# untitled.net
KiCad netlist of a schematic drawn in EAGLE
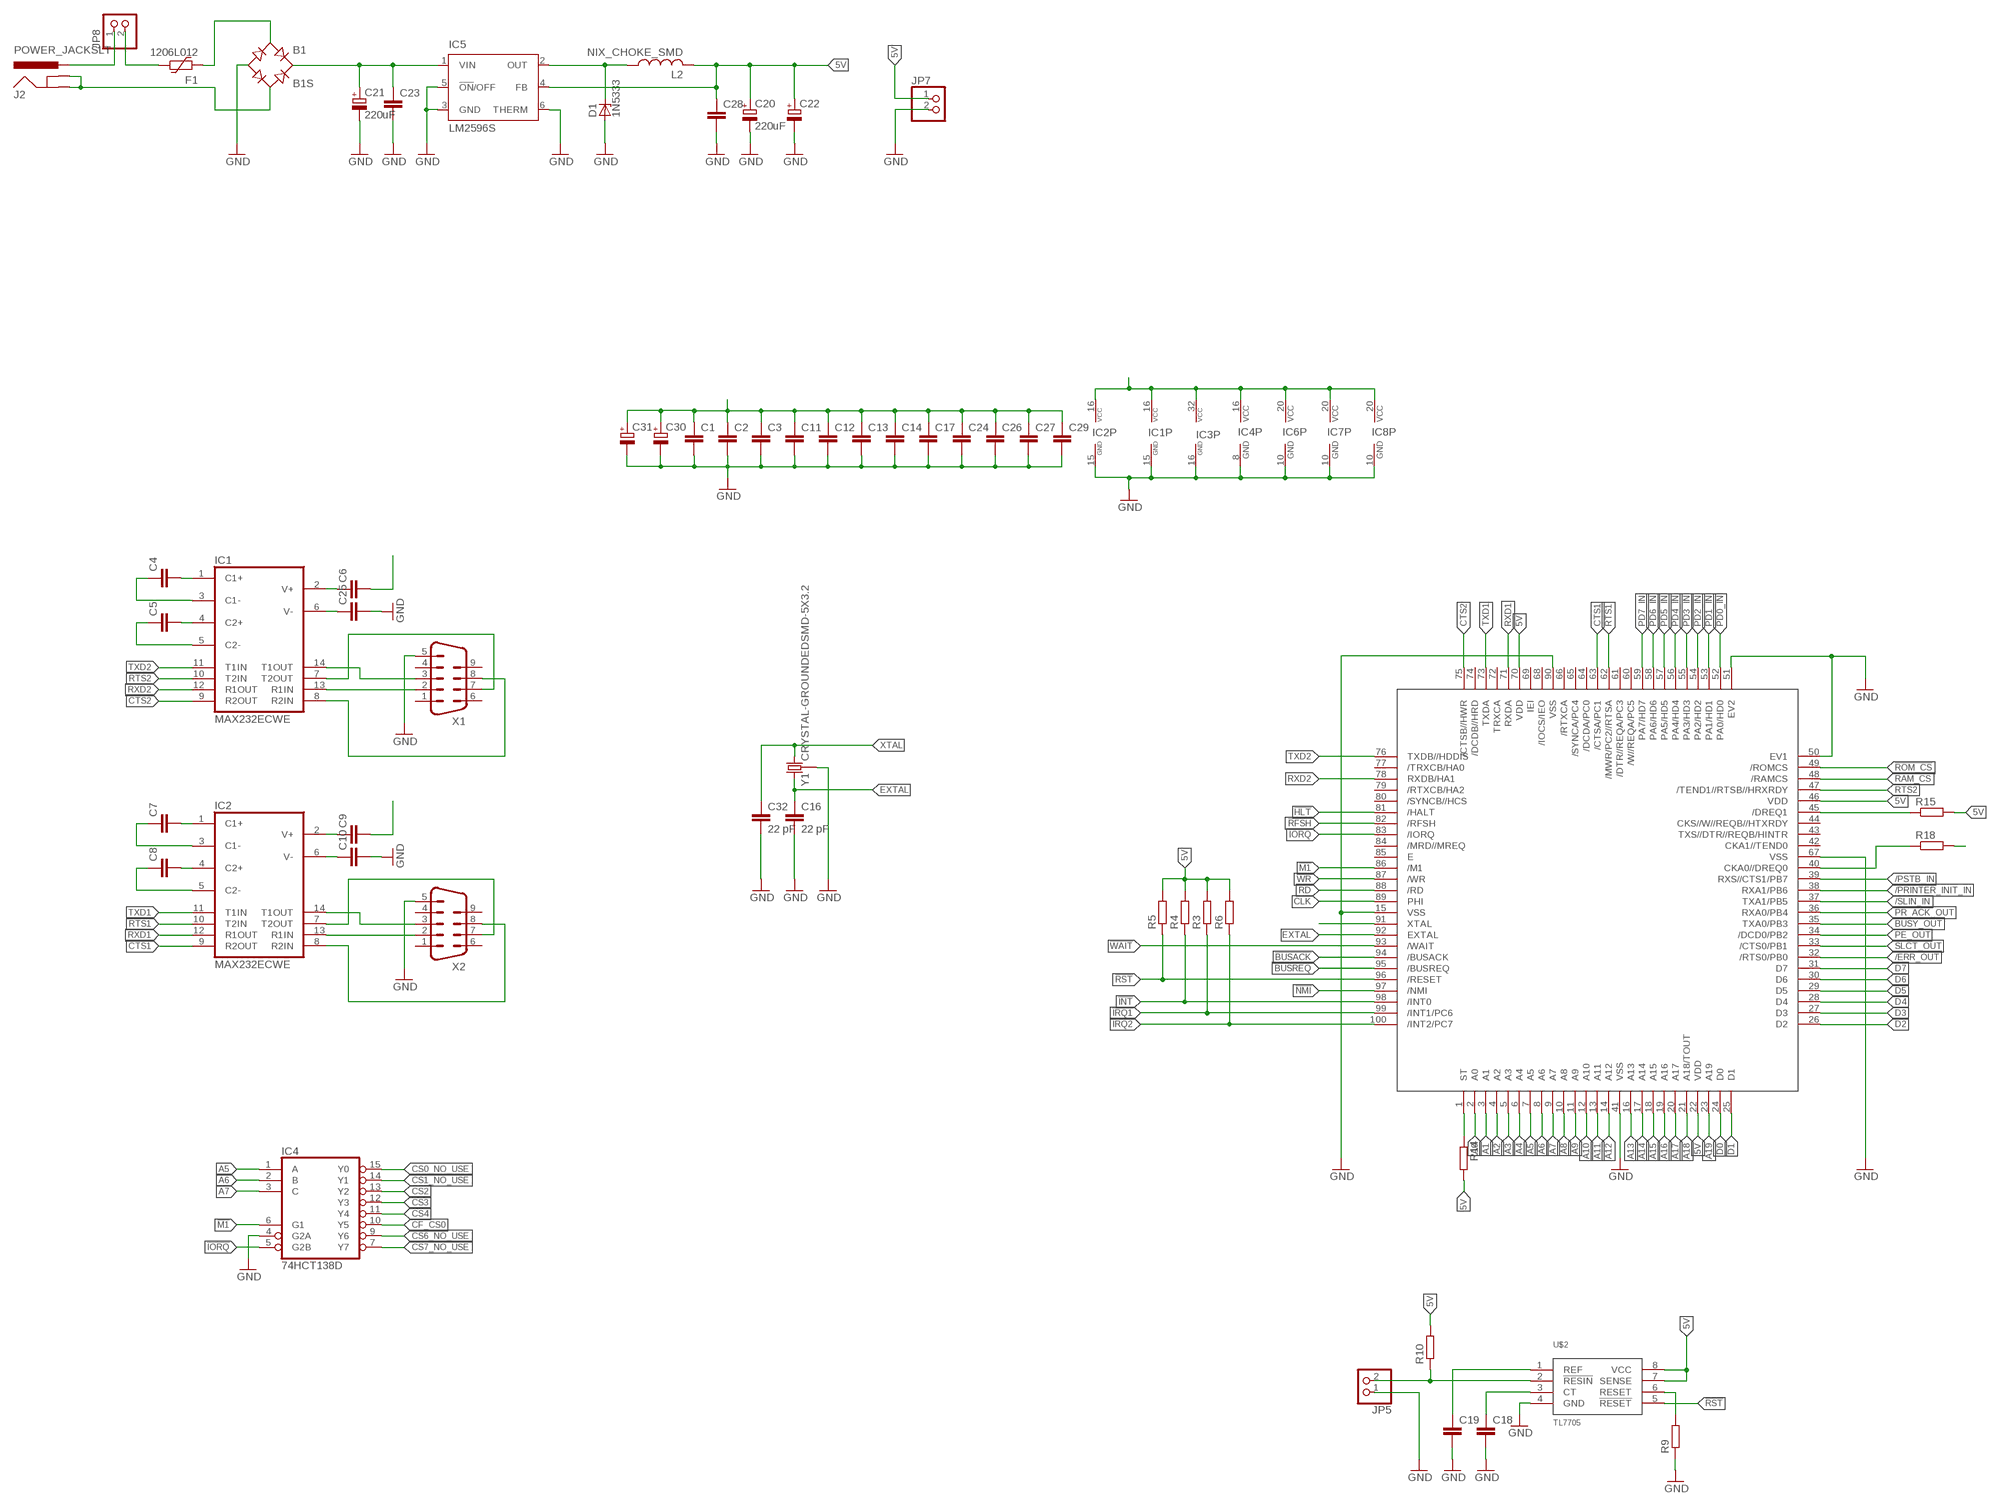
[diagram p0: schematic, sheet 1, part 1 of 2]
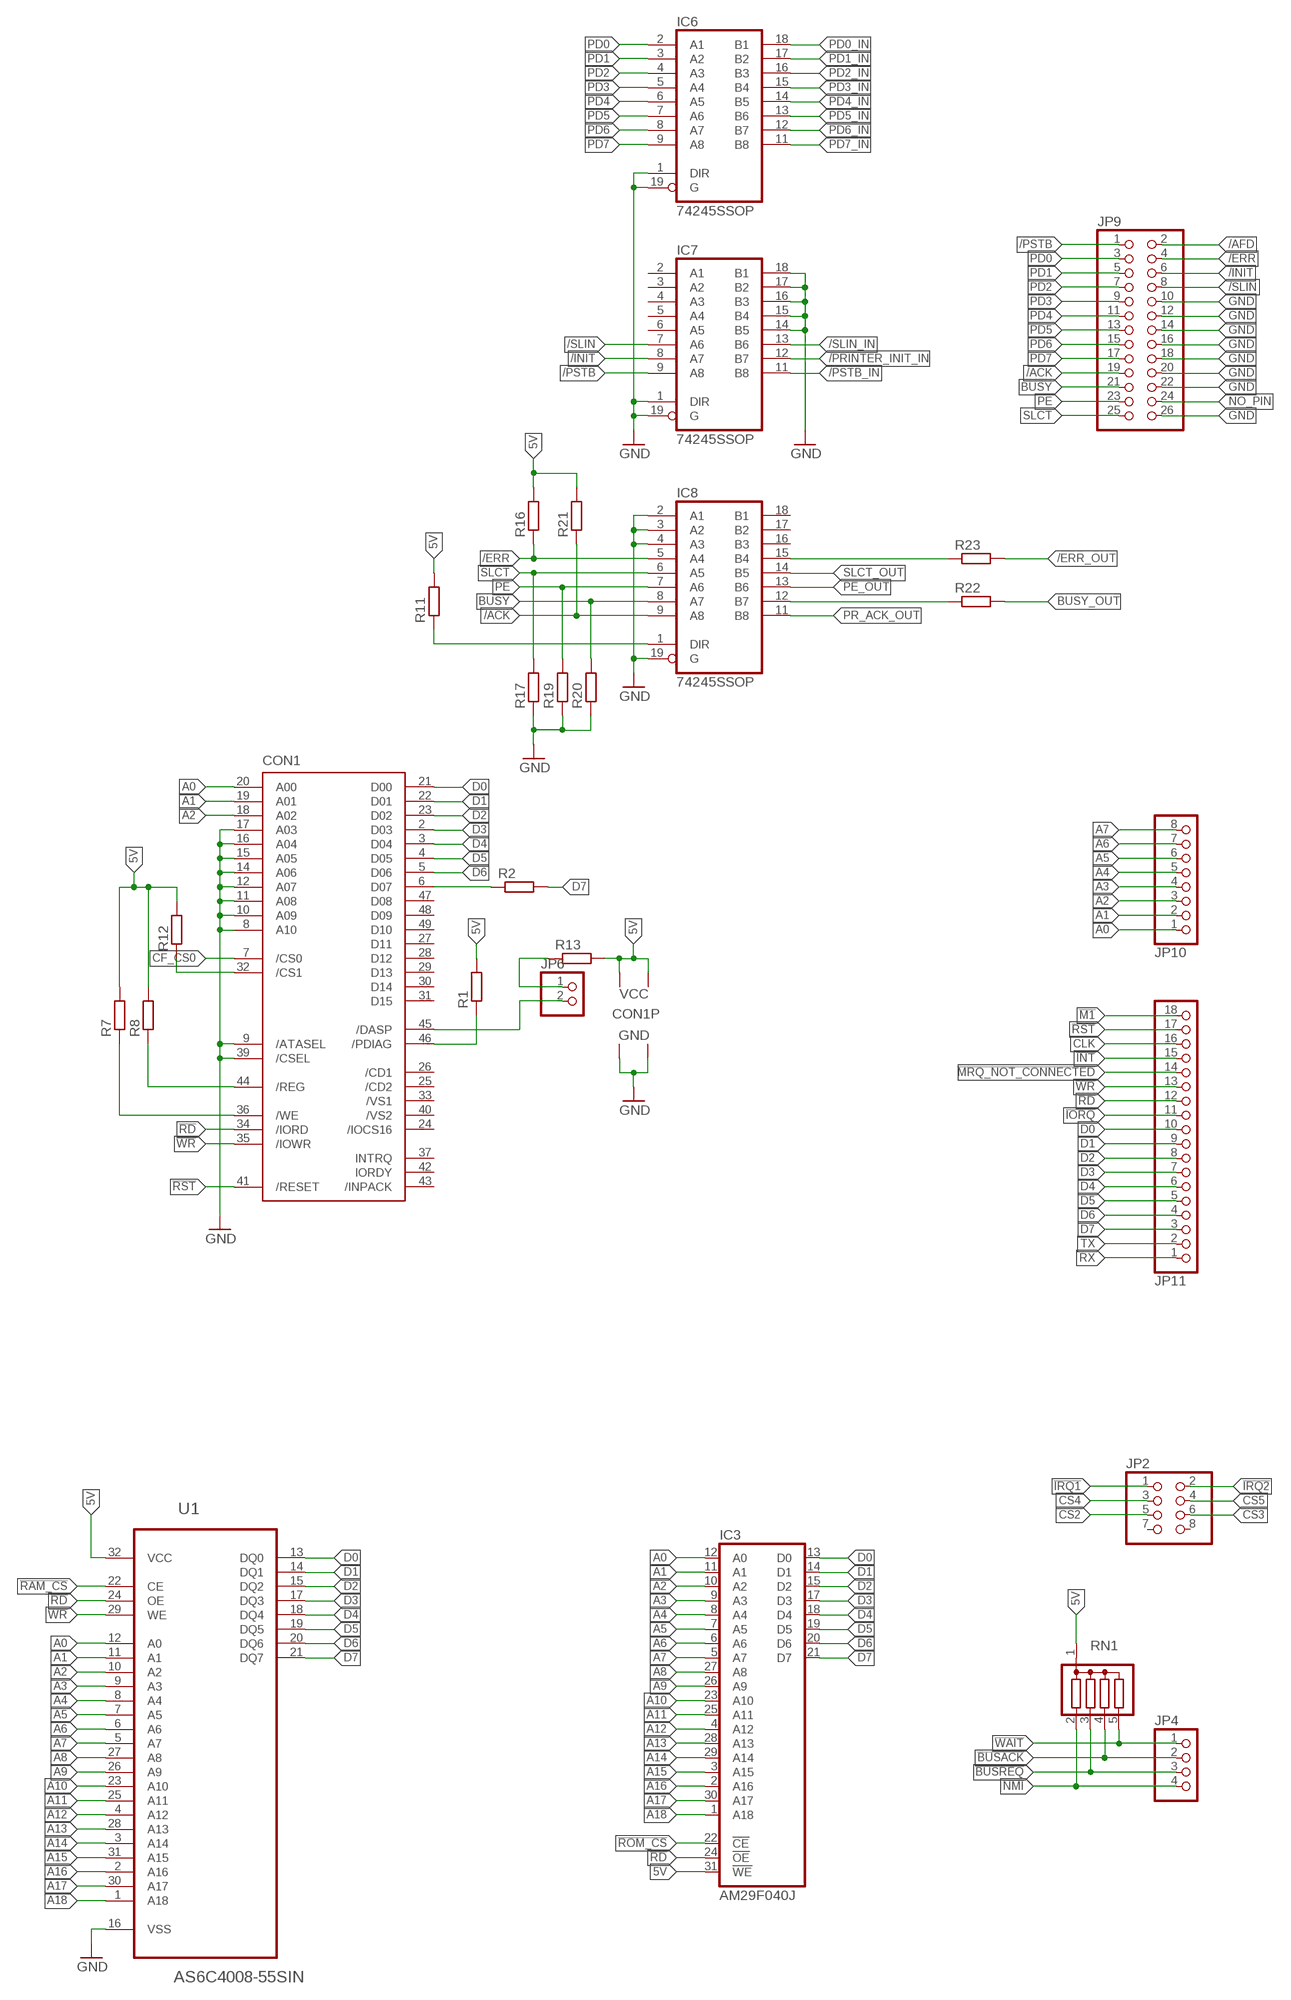
[diagram p1: schematic, sheet 1, part 2 of 2]

(export (version "E")
  (design (tool "Eeschema 10.0.6"))
  (components
    (comp (ref "B1")
      (value "B1S")
      (footprint "eagle-import:MBS")
      (libsource (lib "eagle-import") (part "BS1"))
    )
    (comp (ref "C1")
      (value "C-EUC0603")
      (footprint "eagle-import:C0603")
      (libsource (lib "eagle-import") (part "C-EUC0603"))
    )
    (comp (ref "C2")
      (value "C-EUC0603")
      (footprint "eagle-import:C0603")
      (libsource (lib "eagle-import") (part "C-EUC0603"))
    )
    (comp (ref "C3")
      (value "C-EUC0402")
      (footprint "eagle-import:C0402")
      (libsource (lib "eagle-import") (part "C-EUC0402"))
    )
    (comp (ref "C4")
      (value "C-EUC0603")
      (footprint "eagle-import:C0603")
      (libsource (lib "eagle-import") (part "C-EUC0603"))
    )
    (comp (ref "C5")
      (value "C-EUC0603")
      (footprint "eagle-import:C0603")
      (libsource (lib "eagle-import") (part "C-EUC0603"))
    )
    (comp (ref "C6")
      (value "C-EUC0603")
      (footprint "eagle-import:C0603")
      (libsource (lib "eagle-import") (part "C-EUC0603"))
    )
    (comp (ref "C7")
      (value "C-EUC0603")
      (footprint "eagle-import:C0603")
      (libsource (lib "eagle-import") (part "C-EUC0603"))
    )
    (comp (ref "C8")
      (value "C-EUC0603")
      (footprint "eagle-import:C0603")
      (libsource (lib "eagle-import") (part "C-EUC0603"))
    )
    (comp (ref "C9")
      (value "C-EUC0603")
      (footprint "eagle-import:C0603")
      (libsource (lib "eagle-import") (part "C-EUC0603"))
    )
    (comp (ref "C10")
      (value "C-EUC0603")
      (footprint "eagle-import:C0603")
      (libsource (lib "eagle-import") (part "C-EUC0603"))
    )
    (comp (ref "C11")
      (value "C-EUC0603")
      (footprint "eagle-import:C0603")
      (libsource (lib "eagle-import") (part "C-EUC0603"))
    )
    (comp (ref "C12")
      (value "C-EUC0603")
      (footprint "eagle-import:C0603")
      (libsource (lib "eagle-import") (part "C-EUC0603"))
    )
    (comp (ref "C13")
      (value "C-EUC0402")
      (footprint "eagle-import:C0402")
      (libsource (lib "eagle-import") (part "C-EUC0402"))
    )
    (comp (ref "C14")
      (value "C-EUC0603")
      (footprint "eagle-import:C0603")
      (libsource (lib "eagle-import") (part "C-EUC0603"))
    )
    (comp (ref "C16")
      (value "22 pF")
      (footprint "eagle-import:C0603")
      (libsource (lib "eagle-import") (part "C-EUC0603"))
    )
    (comp (ref "C17")
      (value "C-EUC0603")
      (footprint "eagle-import:C0603")
      (libsource (lib "eagle-import") (part "C-EUC0603"))
    )
    (comp (ref "C18")
      (value "C-EUC0603")
      (footprint "eagle-import:C0603")
      (libsource (lib "eagle-import") (part "C-EUC0603"))
    )
    (comp (ref "C19")
      (value "C-EUC0603")
      (footprint "eagle-import:C0603")
      (libsource (lib "eagle-import") (part "C-EUC0603"))
    )
    (comp (ref "C20")
      (value "220uF")
      (footprint "eagle-import:153CLV-0810")
      (libsource (lib "eagle-import") (part "CPOL-EU153CLV-0810"))
    )
    (comp (ref "C21")
      (value "220uF")
      (footprint "eagle-import:153CLV-0810")
      (libsource (lib "eagle-import") (part "CPOL-EU153CLV-0810"))
    )
    (comp (ref "C22")
      (value "CPOL-EUSMCC")
      (footprint "eagle-import:SMC_C")
      (libsource (lib "eagle-import") (part "CPOL-EUSMCC"))
    )
    (comp (ref "C23")
      (value "C-EUC0603")
      (footprint "eagle-import:C0603")
      (libsource (lib "eagle-import") (part "C-EUC0603"))
    )
    (comp (ref "C24")
      (value "C-EUC0603")
      (footprint "eagle-import:C0603")
      (libsource (lib "eagle-import") (part "C-EUC0603"))
    )
    (comp (ref "C25")
      (value "C-EUC0603")
      (footprint "eagle-import:C0603")
      (libsource (lib "eagle-import") (part "C-EUC0603"))
    )
    (comp (ref "C26")
      (value "C-EUC0402")
      (footprint "eagle-import:C0402")
      (libsource (lib "eagle-import") (part "C-EUC0402"))
    )
    (comp (ref "C27")
      (value "C-EUC0402")
      (footprint "eagle-import:C0402")
      (libsource (lib "eagle-import") (part "C-EUC0402"))
    )
    (comp (ref "C28")
      (value "C-EUC0603")
      (footprint "eagle-import:C0603")
      (libsource (lib "eagle-import") (part "C-EUC0603"))
    )
    (comp (ref "C29")
      (value "C-EUC0603")
      (footprint "eagle-import:C0603")
      (libsource (lib "eagle-import") (part "C-EUC0603"))
    )
    (comp (ref "C30")
      (value "CPOL-EUSMCB")
      (footprint "eagle-import:SMC_B")
      (libsource (lib "eagle-import") (part "CPOL-EUSMCB"))
    )
    (comp (ref "C31")
      (value "CPOL-EUSMCB")
      (footprint "eagle-import:SMC_B")
      (libsource (lib "eagle-import") (part "CPOL-EUSMCB"))
    )
    (comp (ref "C32")
      (value "22 pF")
      (footprint "eagle-import:C0603")
      (libsource (lib "eagle-import") (part "C-EUC0603"))
    )
    (comp (ref "CON1")
      (value "CF-CARD-IDE_MODE")
      (footprint "eagle-import:MI20-50PD-SF")
      (libsource (lib "eagle-import") (part "CF-CARD-IDE_MODE"))
    )
    (comp (ref "D1")
      (value "1N5333")
      (footprint "eagle-import:C1702-15")
      (libsource (lib "eagle-import") (part "1N5333"))
    )
    (comp (ref "F1")
      (value "1206L012")
      (footprint "eagle-import:1206L")
      (fields (field (name "MF") "Littelfuse"))
      (libsource (lib "eagle-import") (part "?1206L012"))
    )
    (comp (ref "IC1")
      (value "MAX232ECWE")
      (footprint "eagle-import:SO16L")
      (fields (field (name "MF") "MAXIM") (field (name "MPN") "MAX232ECWE+"))
      (libsource (lib "eagle-import") (part "MAX232ECWE"))
    )
    (comp (ref "IC2")
      (value "MAX232ECWE")
      (footprint "eagle-import:SO16L")
      (fields (field (name "MF") "MAXIM") (field (name "MPN") "MAX232ECWE+"))
      (libsource (lib "eagle-import") (part "MAX232ECWE"))
    )
    (comp (ref "IC3")
      (value "AM29F040J")
      (footprint "eagle-import:PLCC32R")
      (libsource (lib "eagle-import") (part "AM29F040J"))
    )
    (comp (ref "IC4")
      (value "74HCT138D")
      (footprint "eagle-import:SO16")
      (libsource (lib "eagle-import") (part "74138DHCT"))
    )
    (comp (ref "IC5")
      (value "LM2596S")
      (footprint "eagle-import:TO263-5")
      (fields (field (name "MF") "NATIONAL SEMICONDUCTOR") (field (name "MPN") "LM2596S-ADJ/NOPB"))
      (libsource (lib "eagle-import") (part "LM2596S"))
    )
    (comp (ref "IC6")
      (value "74245SSOP")
      (footprint "eagle-import:SSOP20")
      (libsource (lib "eagle-import") (part "74245SSOP"))
    )
    (comp (ref "IC7")
      (value "74245SSOP")
      (footprint "eagle-import:SSOP20")
      (libsource (lib "eagle-import") (part "74245SSOP"))
    )
    (comp (ref "IC8")
      (value "74245SSOP")
      (footprint "eagle-import:SSOP20")
      (libsource (lib "eagle-import") (part "74245SSOP"))
    )
    (comp (ref "J2")
      (value "POWER_JACKSLT")
      (footprint "eagle-import:POWER_JACK_SLOT")
      (libsource (lib "eagle-import") (part "POWER_JACKSLT"))
    )
    (comp (ref "JP2")
      (value "PINHD-2X4")
      (footprint "eagle-import:2X04")
      (libsource (lib "eagle-import") (part "PINHD-2X4"))
    )
    (comp (ref "JP4")
      (value "PINHD-1X4")
      (footprint "eagle-import:1X04")
      (libsource (lib "eagle-import") (part "PINHD-1X4"))
    )
    (comp (ref "JP5")
      (value "PINHD-1X2")
      (footprint "eagle-import:1X02")
      (libsource (lib "eagle-import") (part "PINHD-1X2"))
    )
    (comp (ref "JP6")
      (value "PINHD-1X2")
      (footprint "eagle-import:1X02")
      (libsource (lib "eagle-import") (part "PINHD-1X2"))
    )
    (comp (ref "JP7")
      (value "PINHD-1X2")
      (footprint "eagle-import:1X02")
      (libsource (lib "eagle-import") (part "PINHD-1X2"))
    )
    (comp (ref "JP8")
      (value "PINHD-1X2")
      (footprint "eagle-import:1X02")
      (libsource (lib "eagle-import") (part "PINHD-1X2"))
    )
    (comp (ref "JP9")
      (value "PINHD-2X13_2.54-SMD")
      (footprint "eagle-import:2X13SMD")
      (libsource (lib "eagle-import") (part "PINHD-2X13_2.54-SMD"))
    )
    (comp (ref "JP10")
      (value "PINHD-1X8")
      (footprint "eagle-import:1X08")
      (libsource (lib "eagle-import") (part "PINHD-1X8"))
    )
    (comp (ref "JP11")
      (value "PINHD-1X18")
      (footprint "eagle-import:1X18")
      (libsource (lib "eagle-import") (part "PINHD-1X18"))
    )
    (comp (ref "L2")
      (value "NIX_CHOKE_SMD")
      (footprint "eagle-import:NIX_CHOKE_SMD")
      (libsource (lib "eagle-import") (part "NIX_CHOKE_SMD"))
    )
    (comp (ref "R1")
      (value "R-EU_R0603")
      (footprint "eagle-import:R0603")
      (libsource (lib "eagle-import") (part "R-EU_R0603"))
    )
    (comp (ref "R2")
      (value "R-EU_R0603")
      (footprint "eagle-import:R0603")
      (libsource (lib "eagle-import") (part "R-EU_R0603"))
    )
    (comp (ref "R3")
      (value "R-EU_R0402")
      (footprint "eagle-import:R0402")
      (libsource (lib "eagle-import") (part "R-EU_R0402"))
    )
    (comp (ref "R4")
      (value "R-EU_R0603")
      (footprint "eagle-import:R0603")
      (libsource (lib "eagle-import") (part "R-EU_R0603"))
    )
    (comp (ref "R5")
      (value "R-EU_R1206")
      (footprint "eagle-import:R1206")
      (libsource (lib "eagle-import") (part "R-EU_R1206"))
    )
    (comp (ref "R6")
      (value "R-EU_R0603")
      (footprint "eagle-import:R0603")
      (libsource (lib "eagle-import") (part "R-EU_R0603"))
    )
    (comp (ref "R7")
      (value "R-EU_R0603")
      (footprint "eagle-import:R0603")
      (libsource (lib "eagle-import") (part "R-EU_R0603"))
    )
    (comp (ref "R8")
      (value "R-EU_R0603")
      (footprint "eagle-import:R0603")
      (libsource (lib "eagle-import") (part "R-EU_R0603"))
    )
    (comp (ref "R9")
      (value "R-EU_R0603")
      (footprint "eagle-import:R0603")
      (libsource (lib "eagle-import") (part "R-EU_R0603"))
    )
    (comp (ref "R10")
      (value "R-EU_M1206")
      (footprint "eagle-import:M1206")
      (libsource (lib "eagle-import") (part "R-EU_M1206"))
    )
    (comp (ref "R11")
      (value "R-EU_R0603")
      (footprint "eagle-import:R0603")
      (libsource (lib "eagle-import") (part "R-EU_R0603"))
    )
    (comp (ref "R12")
      (value "R-EU_R0603")
      (footprint "eagle-import:R0603")
      (libsource (lib "eagle-import") (part "R-EU_R0603"))
    )
    (comp (ref "R13")
      (value "R-EU_R0603")
      (footprint "eagle-import:R0603")
      (libsource (lib "eagle-import") (part "R-EU_R0603"))
    )
    (comp (ref "R14")
      (value "R-EU_0204/5")
      (footprint "eagle-import:0204_5")
      (libsource (lib "eagle-import") (part "R-EU_0204/5"))
    )
    (comp (ref "R15")
      (value "R-EU_R0402")
      (footprint "eagle-import:R0402")
      (libsource (lib "eagle-import") (part "R-EU_R0402"))
    )
    (comp (ref "R16")
      (value "R-EU_R0603")
      (footprint "eagle-import:R0603")
      (libsource (lib "eagle-import") (part "R-EU_R0603"))
    )
    (comp (ref "R17")
      (value "R-EU_R0603")
      (footprint "eagle-import:R0603")
      (libsource (lib "eagle-import") (part "R-EU_R0603"))
    )
    (comp (ref "R18")
      (value "R-EU_R0402")
      (footprint "eagle-import:R0402")
      (libsource (lib "eagle-import") (part "R-EU_R0402"))
    )
    (comp (ref "R19")
      (value "R-EU_R0603")
      (footprint "eagle-import:R0603")
      (libsource (lib "eagle-import") (part "R-EU_R0603"))
    )
    (comp (ref "R20")
      (value "R-EU_R0603")
      (footprint "eagle-import:R0603")
      (libsource (lib "eagle-import") (part "R-EU_R0603"))
    )
    (comp (ref "R21")
      (value "R-EU_R0603")
      (footprint "eagle-import:R0603")
      (libsource (lib "eagle-import") (part "R-EU_R0603"))
    )
    (comp (ref "R22")
      (value "R-EU_R0402")
      (footprint "eagle-import:R0402")
      (libsource (lib "eagle-import") (part "R-EU_R0402"))
    )
    (comp (ref "R23")
      (value "R-EU_R0402")
      (footprint "eagle-import:R0402")
      (libsource (lib "eagle-import") (part "R-EU_R0402"))
    )
    (comp (ref "RN1")
      (value "G04R")
      (footprint "eagle-import:SIL5")
      (libsource (lib "eagle-import") (part "G04R"))
    )
    (comp (ref "U$1")
      (value "Z80182")
      (footprint "eagle-import:TQFP100")
      (libsource (lib "eagle-import") (part "Z80182"))
    )
    (comp (ref "U$2")
      (value "TL7705")
      (footprint "eagle-import:SOIC8")
      (libsource (lib "eagle-import") (part "TL7705"))
    )
    (comp (ref "U1")
      (value "AS6C4008-55SIN")
      (footprint "eagle-import:SOIC127P1407X299-32N")
      (libsource (lib "eagle-import") (part "AS6C4008-55SIN"))
    )
    (comp (ref "X1")
      (value "M09HP")
      (footprint "eagle-import:M09HP")
      (libsource (lib "eagle-import") (part "M09HP"))
    )
    (comp (ref "X2")
      (value "M09HP")
      (footprint "eagle-import:M09HP")
      (libsource (lib "eagle-import") (part "M09HP"))
    )
    (comp (ref "Y1")
      (value "CRYSTAL-GROUNDEDSMD-5X3.2")
      (footprint "eagle-import:CRYSTAL-SMD-5X3.2-4PAD")
      (libsource (lib "eagle-import") (part "CRYSTAL-GROUNDEDSMD-5X3.2"))
    )
  )
  (nets
    (net (code "1") (name "/~{BUSACK}") (class "Default")
      (node (ref "JP4") (pin "2") (pinfunction "2_2") (pintype "passive"))
      (node (ref "RN1") (pin "4") (pinfunction "4_4") (pintype "passive"))
      (node (ref "U$1") (pin "94") (pinfunction "/BUSACK_94") (pintype "bidirectional"))
    )
    (net (code "2") (name "/~{BUSREQ}") (class "Default")
      (node (ref "JP4") (pin "3") (pinfunction "3_3") (pintype "passive"))
      (node (ref "RN1") (pin "3") (pinfunction "3_3") (pintype "passive"))
      (node (ref "U$1") (pin "95") (pinfunction "/BUSREQ_95") (pintype "bidirectional"))
    )
    (net (code "3") (name "/~{HLT}") (class "Default")
      (node (ref "U$1") (pin "81") (pinfunction "/HALT_81") (pintype "bidirectional"))
    )
    (net (code "4") (name "/~{INT}") (class "Default")
      (node (ref "JP11") (pin "15") (pinfunction "15_15") (pintype "passive"))
      (node (ref "R4") (pin "1") (pinfunction "1_1") (pintype "passive"))
      (node (ref "U$1") (pin "98") (pinfunction "/INT0_98") (pintype "bidirectional"))
    )
    (net (code "5") (name "/~{IORQ}") (class "Default")
      (node (ref "IC4") (pin "5") (pinfunction "G2B_5") (pintype "input"))
      (node (ref "JP11") (pin "11") (pinfunction "11_11") (pintype "passive"))
      (node (ref "U$1") (pin "83") (pinfunction "/IORQ_83") (pintype "bidirectional"))
    )
    (net (code "6") (name "/~{IRQ1}") (class "Default")
      (node (ref "JP2") (pin "1") (pinfunction "1_1") (pintype "passive"))
      (node (ref "R3") (pin "1") (pinfunction "1_1") (pintype "passive"))
      (node (ref "U$1") (pin "99") (pinfunction "/INT1/PC6_99") (pintype "bidirectional"))
    )
    (net (code "7") (name "/~{IRQ2}") (class "Default")
      (node (ref "JP2") (pin "2") (pinfunction "2_2") (pintype "passive"))
      (node (ref "R6") (pin "1") (pinfunction "1_1") (pintype "passive"))
      (node (ref "U$1") (pin "100") (pinfunction "/INT2/PC7_100") (pintype "bidirectional"))
    )
    (net (code "8") (name "/~{M1}") (class "Default")
      (node (ref "IC4") (pin "6") (pinfunction "G1_6") (pintype "input"))
      (node (ref "JP11") (pin "18") (pinfunction "18_18") (pintype "passive"))
      (node (ref "U$1") (pin "86") (pinfunction "/M1_86") (pintype "bidirectional"))
    )
    (net (code "9") (name "/~{MRQ_NOT_CONNECTED}") (class "Default")
      (node (ref "JP11") (pin "14") (pinfunction "14_14") (pintype "passive"))
    )
    (net (code "10") (name "/~{NMI}") (class "Default")
      (node (ref "JP4") (pin "4") (pinfunction "4_4") (pintype "passive"))
      (node (ref "RN1") (pin "2") (pinfunction "2_2") (pintype "passive"))
      (node (ref "U$1") (pin "97") (pinfunction "/NMI_97") (pintype "bidirectional"))
    )
    (net (code "11") (name "/~{RAM_CS}") (class "Default")
      (node (ref "U$1") (pin "48") (pinfunction "/RAMCS_48") (pintype "bidirectional"))
      (node (ref "U1") (pin "22") (pinfunction "CE_22") (pintype "input"))
    )
    (net (code "12") (name "/~{RD}") (class "Default")
      (node (ref "CON1") (pin "34") (pinfunction "/IORD_34") (pintype "input"))
      (node (ref "IC3") (pin "24") (pinfunction "~{OE}_24") (pintype "input"))
      (node (ref "JP11") (pin "12") (pinfunction "12_12") (pintype "passive"))
      (node (ref "U$1") (pin "88") (pinfunction "/RD_88") (pintype "bidirectional"))
      (node (ref "U1") (pin "24") (pinfunction "OE_24") (pintype "input"))
    )
    (net (code "13") (name "/~{RFSH}") (class "Default")
      (node (ref "U$1") (pin "82") (pinfunction "/RFSH_82") (pintype "bidirectional"))
    )
    (net (code "14") (name "/~{ROM_CS}") (class "Default")
      (node (ref "IC3") (pin "22") (pinfunction "~{CE}_22") (pintype "input"))
      (node (ref "U$1") (pin "49") (pinfunction "/ROMCS_49") (pintype "bidirectional"))
    )
    (net (code "15") (name "/~{RST}") (class "Default")
      (node (ref "CON1") (pin "41") (pinfunction "/RESET_41") (pintype "input"))
      (node (ref "JP11") (pin "17") (pinfunction "17_17") (pintype "passive"))
      (node (ref "R5") (pin "1") (pinfunction "1_1") (pintype "passive"))
      (node (ref "U$1") (pin "96") (pinfunction "/RESET_96") (pintype "bidirectional"))
      (node (ref "U$2") (pin "5") (pinfunction "~{RESET}_5") (pintype "bidirectional"))
    )
    (net (code "16") (name "/~{WAIT}") (class "Default")
      (node (ref "JP4") (pin "1") (pinfunction "1_1") (pintype "passive"))
      (node (ref "RN1") (pin "5") (pinfunction "5_5") (pintype "passive"))
      (node (ref "U$1") (pin "93") (pinfunction "/WAIT_93") (pintype "bidirectional"))
    )
    (net (code "17") (name "/~{WR}") (class "Default")
      (node (ref "CON1") (pin "35") (pinfunction "/IOWR_35") (pintype "input"))
      (node (ref "JP11") (pin "13") (pinfunction "13_13") (pintype "passive"))
      (node (ref "U$1") (pin "87") (pinfunction "/WR_87") (pintype "bidirectional"))
      (node (ref "U1") (pin "29") (pinfunction "WE_29") (pintype "input"))
    )
    (net (code "18") (name "5V") (class "Default")
      (node (ref "C1") (pin "1") (pinfunction "1_1") (pintype "passive"))
      (node (ref "C11") (pin "1") (pinfunction "1_1") (pintype "passive"))
      (node (ref "C12") (pin "1") (pinfunction "1_1") (pintype "passive"))
      (node (ref "C13") (pin "1") (pinfunction "1_1") (pintype "passive"))
      (node (ref "C14") (pin "1") (pinfunction "1_1") (pintype "passive"))
      (node (ref "C17") (pin "1") (pinfunction "1_1") (pintype "passive"))
      (node (ref "C2") (pin "1") (pinfunction "1_1") (pintype "passive"))
      (node (ref "C20") (pin "+") (pinfunction "+_+") (pintype "passive"))
      (node (ref "C22") (pin "+") (pinfunction "+_+") (pintype "passive"))
      (node (ref "C24") (pin "1") (pinfunction "1_1") (pintype "passive"))
      (node (ref "C26") (pin "1") (pinfunction "1_1") (pintype "passive"))
      (node (ref "C27") (pin "1") (pinfunction "1_1") (pintype "passive"))
      (node (ref "C28") (pin "1") (pinfunction "1_1") (pintype "passive"))
      (node (ref "C29") (pin "1") (pinfunction "1_1") (pintype "passive"))
      (node (ref "C3") (pin "1") (pinfunction "1_1") (pintype "passive"))
      (node (ref "C30") (pin "+") (pinfunction "+_+") (pintype "passive"))
      (node (ref "C31") (pin "+") (pinfunction "+_+") (pintype "passive"))
      (node (ref "C6") (pin "2") (pinfunction "2_2") (pintype "passive"))
      (node (ref "C9") (pin "2") (pinfunction "2_2") (pintype "passive"))
      (node (ref "CON1") (pin "13") (pinfunction "VCC2_13") (pintype "power_in"))
      (node (ref "CON1") (pin "38") (pinfunction "VCC1_38") (pintype "power_in"))
      (node (ref "IC1") (pin "16") (pinfunction "VCC_16") (pintype "power_in"))
      (node (ref "IC2") (pin "16") (pinfunction "VCC_16") (pintype "power_in"))
      (node (ref "IC3") (pin "31") (pinfunction "~{WE}_31") (pintype "input"))
      (node (ref "IC3") (pin "32") (pinfunction "VCC_32") (pintype "power_in"))
      (node (ref "IC4") (pin "16") (pinfunction "VCC_16") (pintype "power_in"))
      (node (ref "IC5") (pin "4") (pinfunction "FB_4") (pintype "input"))
      (node (ref "IC6") (pin "20") (pinfunction "VCC_20") (pintype "power_in"))
      (node (ref "IC7") (pin "20") (pinfunction "VCC_20") (pintype "power_in"))
      (node (ref "IC8") (pin "20") (pinfunction "VCC_20") (pintype "power_in"))
      (node (ref "JP7") (pin "1") (pinfunction "1_1") (pintype "passive"))
      (node (ref "L2") (pin "P$2") (pinfunction "2_P$2") (pintype "passive"))
      (node (ref "R1") (pin "2") (pinfunction "2_2") (pintype "passive"))
      (node (ref "R10") (pin "2") (pinfunction "2_2") (pintype "passive"))
      (node (ref "R11") (pin "2") (pinfunction "2_2") (pintype "passive"))
      (node (ref "R12") (pin "2") (pinfunction "2_2") (pintype "passive"))
      (node (ref "R13") (pin "2") (pinfunction "2_2") (pintype "passive"))
      (node (ref "R14") (pin "2") (pinfunction "2_2") (pintype "passive"))
      (node (ref "R15") (pin "2") (pinfunction "2_2") (pintype "passive"))
      (node (ref "R16") (pin "2") (pinfunction "2_2") (pintype "passive"))
      (node (ref "R18") (pin "2") (pinfunction "2_2") (pintype "passive"))
      (node (ref "R21") (pin "2") (pinfunction "2_2") (pintype "passive"))
      (node (ref "R3") (pin "2") (pinfunction "2_2") (pintype "passive"))
      (node (ref "R4") (pin "2") (pinfunction "2_2") (pintype "passive"))
      (node (ref "R5") (pin "2") (pinfunction "2_2") (pintype "passive"))
      (node (ref "R6") (pin "2") (pinfunction "2_2") (pintype "passive"))
      (node (ref "R7") (pin "2") (pinfunction "2_2") (pintype "passive"))
      (node (ref "R8") (pin "2") (pinfunction "2_2") (pintype "passive"))
      (node (ref "RN1") (pin "1") (pinfunction "1_1") (pintype "passive"))
      (node (ref "U$1") (pin "22") (pinfunction "VDD_22") (pintype "bidirectional"))
      (node (ref "U$1") (pin "46") (pinfunction "VDD_46") (pintype "bidirectional"))
      (node (ref "U$1") (pin "70") (pinfunction "VDD_70") (pintype "bidirectional"))
      (node (ref "U$2") (pin "7") (pinfunction "SENSE_7") (pintype "bidirectional"))
      (node (ref "U$2") (pin "8") (pinfunction "VCC_8") (pintype "bidirectional"))
      (node (ref "U1") (pin "32") (pinfunction "VCC_32") (pintype "power_in"))
    )
    (net (code "19") (name "A0") (class "Default")
      (node (ref "CON1") (pin "20") (pinfunction "A00_20") (pintype "input"))
      (node (ref "IC3") (pin "12") (pinfunction "A0_12") (pintype "input"))
      (node (ref "JP10") (pin "1") (pinfunction "1_1") (pintype "passive"))
      (node (ref "U$1") (pin "2") (pinfunction "A0_2") (pintype "bidirectional"))
      (node (ref "U1") (pin "12") (pinfunction "A0_12") (pintype "input"))
    )
    (net (code "20") (name "A1") (class "Default")
      (node (ref "CON1") (pin "19") (pinfunction "A01_19") (pintype "input"))
      (node (ref "IC3") (pin "11") (pinfunction "A1_11") (pintype "input"))
      (node (ref "JP10") (pin "2") (pinfunction "2_2") (pintype "passive"))
      (node (ref "U$1") (pin "3") (pinfunction "A1_3") (pintype "bidirectional"))
      (node (ref "U1") (pin "11") (pinfunction "A1_11") (pintype "input"))
    )
    (net (code "21") (name "A2") (class "Default")
      (node (ref "CON1") (pin "18") (pinfunction "A02_18") (pintype "input"))
      (node (ref "IC3") (pin "10") (pinfunction "A2_10") (pintype "input"))
      (node (ref "JP10") (pin "3") (pinfunction "3_3") (pintype "passive"))
      (node (ref "U$1") (pin "4") (pinfunction "A2_4") (pintype "bidirectional"))
      (node (ref "U1") (pin "10") (pinfunction "A2_10") (pintype "input"))
    )
    (net (code "22") (name "A3") (class "Default")
      (node (ref "IC3") (pin "9") (pinfunction "A3_9") (pintype "input"))
      (node (ref "JP10") (pin "4") (pinfunction "4_4") (pintype "passive"))
      (node (ref "U$1") (pin "5") (pinfunction "A3_5") (pintype "bidirectional"))
      (node (ref "U1") (pin "9") (pinfunction "A3_9") (pintype "input"))
    )
    (net (code "23") (name "A4") (class "Default")
      (node (ref "IC3") (pin "8") (pinfunction "A4_8") (pintype "input"))
      (node (ref "JP10") (pin "5") (pinfunction "5_5") (pintype "passive"))
      (node (ref "U$1") (pin "6") (pinfunction "A4_6") (pintype "bidirectional"))
      (node (ref "U1") (pin "8") (pinfunction "A4_8") (pintype "input"))
    )
    (net (code "24") (name "A5") (class "Default")
      (node (ref "IC3") (pin "7") (pinfunction "A5_7") (pintype "input"))
      (node (ref "IC4") (pin "1") (pinfunction "A_1") (pintype "input"))
      (node (ref "JP10") (pin "6") (pinfunction "6_6") (pintype "passive"))
      (node (ref "U$1") (pin "7") (pinfunction "A5_7") (pintype "bidirectional"))
      (node (ref "U1") (pin "7") (pinfunction "A5_7") (pintype "input"))
    )
    (net (code "25") (name "A6") (class "Default")
      (node (ref "IC3") (pin "6") (pinfunction "A6_6") (pintype "input"))
      (node (ref "IC4") (pin "2") (pinfunction "B_2") (pintype "input"))
      (node (ref "JP10") (pin "7") (pinfunction "7_7") (pintype "passive"))
      (node (ref "U$1") (pin "8") (pinfunction "A6_8") (pintype "bidirectional"))
      (node (ref "U1") (pin "6") (pinfunction "A6_6") (pintype "input"))
    )
    (net (code "26") (name "A7") (class "Default")
      (node (ref "IC3") (pin "5") (pinfunction "A7_5") (pintype "input"))
      (node (ref "IC4") (pin "3") (pinfunction "C_3") (pintype "input"))
      (node (ref "JP10") (pin "8") (pinfunction "8_8") (pintype "passive"))
      (node (ref "U$1") (pin "9") (pinfunction "A7_9") (pintype "bidirectional"))
      (node (ref "U1") (pin "5") (pinfunction "A7_5") (pintype "input"))
    )
    (net (code "27") (name "A8") (class "Default")
      (node (ref "IC3") (pin "27") (pinfunction "A8_27") (pintype "input"))
      (node (ref "U$1") (pin "10") (pinfunction "A8_10") (pintype "bidirectional"))
      (node (ref "U1") (pin "27") (pinfunction "A8_27") (pintype "input"))
    )
    (net (code "28") (name "A9") (class "Default")
      (node (ref "IC3") (pin "26") (pinfunction "A9_26") (pintype "input"))
      (node (ref "U$1") (pin "11") (pinfunction "A9_11") (pintype "bidirectional"))
      (node (ref "U1") (pin "26") (pinfunction "A9_26") (pintype "input"))
    )
    (net (code "29") (name "A10") (class "Default")
      (node (ref "IC3") (pin "23") (pinfunction "A10_23") (pintype "input"))
      (node (ref "U$1") (pin "12") (pinfunction "A10_12") (pintype "bidirectional"))
      (node (ref "U1") (pin "23") (pinfunction "A10_23") (pintype "input"))
    )
    (net (code "30") (name "A11") (class "Default")
      (node (ref "IC3") (pin "25") (pinfunction "A11_25") (pintype "input"))
      (node (ref "U$1") (pin "13") (pinfunction "A11_13") (pintype "bidirectional"))
      (node (ref "U1") (pin "25") (pinfunction "A11_25") (pintype "input"))
    )
    (net (code "31") (name "A12") (class "Default")
      (node (ref "IC3") (pin "4") (pinfunction "A12_4") (pintype "input"))
      (node (ref "U$1") (pin "14") (pinfunction "A12_14") (pintype "bidirectional"))
      (node (ref "U1") (pin "4") (pinfunction "A12_4") (pintype "input"))
    )
    (net (code "32") (name "A13") (class "Default")
      (node (ref "IC3") (pin "28") (pinfunction "A13_28") (pintype "input"))
      (node (ref "U$1") (pin "16") (pinfunction "A13_16") (pintype "bidirectional"))
      (node (ref "U1") (pin "28") (pinfunction "A13_28") (pintype "input"))
    )
    (net (code "33") (name "A14") (class "Default")
      (node (ref "IC3") (pin "29") (pinfunction "A14_29") (pintype "input"))
      (node (ref "U$1") (pin "17") (pinfunction "A14_17") (pintype "bidirectional"))
      (node (ref "U1") (pin "3") (pinfunction "A14_3") (pintype "input"))
    )
    (net (code "34") (name "A15") (class "Default")
      (node (ref "IC3") (pin "3") (pinfunction "A15_3") (pintype "input"))
      (node (ref "U$1") (pin "18") (pinfunction "A15_18") (pintype "bidirectional"))
      (node (ref "U1") (pin "31") (pinfunction "A15_31") (pintype "input"))
    )
    (net (code "35") (name "A16") (class "Default")
      (node (ref "IC3") (pin "2") (pinfunction "A16_2") (pintype "input"))
      (node (ref "U$1") (pin "19") (pinfunction "A16_19") (pintype "bidirectional"))
      (node (ref "U1") (pin "2") (pinfunction "A16_2") (pintype "input"))
    )
    (net (code "36") (name "A17") (class "Default")
      (node (ref "IC3") (pin "30") (pinfunction "A17_30") (pintype "input"))
      (node (ref "U$1") (pin "20") (pinfunction "A17_20") (pintype "bidirectional"))
      (node (ref "U1") (pin "30") (pinfunction "A17_30") (pintype "input"))
    )
    (net (code "37") (name "A18") (class "Default")
      (node (ref "IC3") (pin "1") (pinfunction "A18_1") (pintype "input"))
      (node (ref "U$1") (pin "21") (pinfunction "A18/TOUT_21") (pintype "bidirectional"))
      (node (ref "U1") (pin "1") (pinfunction "A18_1") (pintype "input"))
    )
    (net (code "38") (name "A19") (class "Default")
      (node (ref "U$1") (pin "23") (pinfunction "A19_23") (pintype "bidirectional"))
    )
    (net (code "39") (name "BUSY") (class "Default")
      (node (ref "IC8") (pin "8") (pinfunction "A7_8") (pintype "bidirectional"))
      (node (ref "JP9") (pin "21") (pinfunction "21_21") (pintype "passive"))
      (node (ref "R20") (pin "2") (pinfunction "2_2") (pintype "passive"))
    )
    (net (code "40") (name "BUSY_OUT") (class "Default")
      (node (ref "R22") (pin "2") (pinfunction "2_2") (pintype "passive"))
      (node (ref "U$1") (pin "35") (pinfunction "TXA0/PB3_35") (pintype "bidirectional"))
    )
    (net (code "41") (name "CF_CS0") (class "Default")
      (node (ref "CON1") (pin "7") (pinfunction "/CS0_7") (pintype "input"))
      (node (ref "IC4") (pin "10") (pinfunction "Y5_10") (pintype "output"))
    )
    (net (code "42") (name "CLK") (class "Default")
      (node (ref "JP11") (pin "16") (pinfunction "16_16") (pintype "passive"))
      (node (ref "U$1") (pin "89") (pinfunction "PHI_89") (pintype "bidirectional"))
    )
    (net (code "43") (name "CS0_NO_USE") (class "Default")
      (node (ref "IC4") (pin "15") (pinfunction "Y0_15") (pintype "output"))
    )
    (net (code "44") (name "CS1_NO_USE") (class "Default")
      (node (ref "IC4") (pin "14") (pinfunction "Y1_14") (pintype "output"))
    )
    (net (code "45") (name "CS2") (class "Default")
      (node (ref "IC4") (pin "13") (pinfunction "Y2_13") (pintype "output"))
      (node (ref "JP2") (pin "5") (pinfunction "5_5") (pintype "passive"))
    )
    (net (code "46") (name "CS3") (class "Default")
      (node (ref "IC4") (pin "12") (pinfunction "Y3_12") (pintype "output"))
      (node (ref "JP2") (pin "6") (pinfunction "6_6") (pintype "passive"))
    )
    (net (code "47") (name "CS4") (class "Default")
      (node (ref "IC4") (pin "11") (pinfunction "Y4_11") (pintype "output"))
      (node (ref "JP2") (pin "3") (pinfunction "3_3") (pintype "passive"))
    )
    (net (code "48") (name "CS5") (class "Default")
      (node (ref "JP2") (pin "4") (pinfunction "4_4") (pintype "passive"))
    )
    (net (code "49") (name "CS6_NO_USE") (class "Default")
      (node (ref "IC4") (pin "9") (pinfunction "Y6_9") (pintype "output"))
    )
    (net (code "50") (name "CS7_NO_USE") (class "Default")
      (node (ref "IC4") (pin "7") (pinfunction "Y7_7") (pintype "output"))
    )
    (net (code "51") (name "CTS1") (class "Default")
      (node (ref "IC2") (pin "9") (pinfunction "R2OUT_9") (pintype "output"))
      (node (ref "U$1") (pin "63") (pinfunction "/CTSA/PC1_63") (pintype "bidirectional"))
    )
    (net (code "52") (name "CTS2") (class "Default")
      (node (ref "IC1") (pin "9") (pinfunction "R2OUT_9") (pintype "output"))
      (node (ref "U$1") (pin "75") (pinfunction "/CTSB//HWR_75") (pintype "bidirectional"))
    )
    (net (code "53") (name "D0") (class "Default")
      (node (ref "CON1") (pin "21") (pinfunction "D00_21") (pintype "bidirectional"))
      (node (ref "IC3") (pin "13") (pinfunction "D0_13") (pintype "tri_state"))
      (node (ref "JP11") (pin "10") (pinfunction "10_10") (pintype "passive"))
      (node (ref "U$1") (pin "24") (pinfunction "D0_24") (pintype "bidirectional"))
      (node (ref "U1") (pin "13") (pinfunction "DQ0_13") (pintype "output"))
    )
    (net (code "54") (name "D1") (class "Default")
      (node (ref "CON1") (pin "22") (pinfunction "D01_22") (pintype "bidirectional"))
      (node (ref "IC3") (pin "14") (pinfunction "D1_14") (pintype "tri_state"))
      (node (ref "JP11") (pin "9") (pinfunction "9_9") (pintype "passive"))
      (node (ref "U$1") (pin "25") (pinfunction "D1_25") (pintype "bidirectional"))
      (node (ref "U1") (pin "14") (pinfunction "DQ1_14") (pintype "output"))
    )
    (net (code "55") (name "D2") (class "Default")
      (node (ref "CON1") (pin "23") (pinfunction "D02_23") (pintype "bidirectional"))
      (node (ref "IC3") (pin "15") (pinfunction "D2_15") (pintype "tri_state"))
      (node (ref "JP11") (pin "8") (pinfunction "8_8") (pintype "passive"))
      (node (ref "U$1") (pin "26") (pinfunction "D2_26") (pintype "bidirectional"))
      (node (ref "U1") (pin "15") (pinfunction "DQ2_15") (pintype "output"))
    )
    (net (code "56") (name "D3") (class "Default")
      (node (ref "CON1") (pin "2") (pinfunction "D03_2") (pintype "bidirectional"))
      (node (ref "IC3") (pin "17") (pinfunction "D3_17") (pintype "tri_state"))
      (node (ref "JP11") (pin "7") (pinfunction "7_7") (pintype "passive"))
      (node (ref "U$1") (pin "27") (pinfunction "D3_27") (pintype "bidirectional"))
      (node (ref "U1") (pin "17") (pinfunction "DQ3_17") (pintype "output"))
    )
    (net (code "57") (name "D4") (class "Default")
      (node (ref "CON1") (pin "3") (pinfunction "D04_3") (pintype "bidirectional"))
      (node (ref "IC3") (pin "18") (pinfunction "D4_18") (pintype "tri_state"))
      (node (ref "JP11") (pin "6") (pinfunction "6_6") (pintype "passive"))
      (node (ref "U$1") (pin "28") (pinfunction "D4_28") (pintype "bidirectional"))
      (node (ref "U1") (pin "18") (pinfunction "DQ4_18") (pintype "output"))
    )
    (net (code "58") (name "D5") (class "Default")
      (node (ref "CON1") (pin "4") (pinfunction "D05_4") (pintype "bidirectional"))
      (node (ref "IC3") (pin "19") (pinfunction "D5_19") (pintype "tri_state"))
      (node (ref "JP11") (pin "5") (pinfunction "5_5") (pintype "passive"))
      (node (ref "U$1") (pin "29") (pinfunction "D5_29") (pintype "bidirectional"))
      (node (ref "U1") (pin "19") (pinfunction "DQ5_19") (pintype "output"))
    )
    (net (code "59") (name "D6") (class "Default")
      (node (ref "CON1") (pin "5") (pinfunction "D06_5") (pintype "bidirectional"))
      (node (ref "IC3") (pin "20") (pinfunction "D6_20") (pintype "tri_state"))
      (node (ref "JP11") (pin "4") (pinfunction "4_4") (pintype "passive"))
      (node (ref "U$1") (pin "30") (pinfunction "D6_30") (pintype "bidirectional"))
      (node (ref "U1") (pin "20") (pinfunction "DQ6_20") (pintype "output"))
    )
    (net (code "60") (name "D7") (class "Default")
      (node (ref "IC3") (pin "21") (pinfunction "D7_21") (pintype "tri_state"))
      (node (ref "JP11") (pin "3") (pinfunction "3_3") (pintype "passive"))
      (node (ref "R2") (pin "2") (pinfunction "2_2") (pintype "passive"))
      (node (ref "U$1") (pin "31") (pinfunction "D7_31") (pintype "bidirectional"))
      (node (ref "U1") (pin "21") (pinfunction "DQ7_21") (pintype "output"))
    )
    (net (code "61") (name "EXTAL") (class "Default")
      (node (ref "C16") (pin "1") (pinfunction "1_1") (pintype "passive"))
      (node (ref "U$1") (pin "92") (pinfunction "EXTAL_92") (pintype "bidirectional"))
      (node (ref "Y1") (pin "3") (pinfunction "1_3") (pintype "passive"))
    )
    (net (code "62") (name "GND") (class "Default")
      (node (ref "B1") (pin "-") (pinfunction "-_-") (pintype "passive"))
      (node (ref "C1") (pin "2") (pinfunction "2_2") (pintype "passive"))
      (node (ref "C10") (pin "2") (pinfunction "2_2") (pintype "passive"))
      (node (ref "C11") (pin "2") (pinfunction "2_2") (pintype "passive"))
      (node (ref "C12") (pin "2") (pinfunction "2_2") (pintype "passive"))
      (node (ref "C13") (pin "2") (pinfunction "2_2") (pintype "passive"))
      (node (ref "C14") (pin "2") (pinfunction "2_2") (pintype "passive"))
      (node (ref "C16") (pin "2") (pinfunction "2_2") (pintype "passive"))
      (node (ref "C17") (pin "2") (pinfunction "2_2") (pintype "passive"))
      (node (ref "C18") (pin "2") (pinfunction "2_2") (pintype "passive"))
      (node (ref "C19") (pin "2") (pinfunction "2_2") (pintype "passive"))
      (node (ref "C2") (pin "2") (pinfunction "2_2") (pintype "passive"))
      (node (ref "C20") (pin "-") (pinfunction "-_-") (pintype "passive"))
      (node (ref "C21") (pin "-") (pinfunction "-_-") (pintype "passive"))
      (node (ref "C22") (pin "-") (pinfunction "-_-") (pintype "passive"))
      (node (ref "C23") (pin "2") (pinfunction "2_2") (pintype "passive"))
      (node (ref "C24") (pin "2") (pinfunction "2_2") (pintype "passive"))
      (node (ref "C25") (pin "2") (pinfunction "2_2") (pintype "passive"))
      (node (ref "C26") (pin "2") (pinfunction "2_2") (pintype "passive"))
      (node (ref "C27") (pin "2") (pinfunction "2_2") (pintype "passive"))
      (node (ref "C28") (pin "2") (pinfunction "2_2") (pintype "passive"))
      (node (ref "C29") (pin "2") (pinfunction "2_2") (pintype "passive"))
      (node (ref "C3") (pin "2") (pinfunction "2_2") (pintype "passive"))
      (node (ref "C30") (pin "-") (pinfunction "-_-") (pintype "passive"))
      (node (ref "C31") (pin "-") (pinfunction "-_-") (pintype "passive"))
      (node (ref "C32") (pin "2") (pinfunction "2_2") (pintype "passive"))
      (node (ref "CON1") (pin "1") (pinfunction "GND1_1") (pintype "power_in"))
      (node (ref "CON1") (pin "10") (pinfunction "A09_10") (pintype "input"))
      (node (ref "CON1") (pin "11") (pinfunction "A08_11") (pintype "input"))
      (node (ref "CON1") (pin "12") (pinfunction "A07_12") (pintype "input"))
      (node (ref "CON1") (pin "14") (pinfunction "A06_14") (pintype "input"))
      (node (ref "CON1") (pin "15") (pinfunction "A05_15") (pintype "input"))
      (node (ref "CON1") (pin "16") (pinfunction "A04_16") (pintype "input"))
      (node (ref "CON1") (pin "17") (pinfunction "A03_17") (pintype "input"))
      (node (ref "CON1") (pin "39") (pinfunction "/CSEL_39") (pintype "input"))
      (node (ref "CON1") (pin "50") (pinfunction "GND2_50") (pintype "power_in"))
      (node (ref "CON1") (pin "8") (pinfunction "A10_8") (pintype "input"))
      (node (ref "CON1") (pin "9") (pinfunction "/ATASEL_9") (pintype "input"))
      (node (ref "D1") (pin "A") (pinfunction "A_A") (pintype "passive"))
      (node (ref "IC1") (pin "15") (pinfunction "GND_15") (pintype "power_in"))
      (node (ref "IC2") (pin "15") (pinfunction "GND_15") (pintype "power_in"))
      (node (ref "IC3") (pin "16") (pinfunction "GND_16") (pintype "power_in"))
      (node (ref "IC4") (pin "4") (pinfunction "G2A_4") (pintype "input"))
      (node (ref "IC4") (pin "8") (pinfunction "GND_8") (pintype "power_in"))
      (node (ref "IC5") (pin "3") (pinfunction "GND_3") (pintype "power_in"))
      (node (ref "IC5") (pin "5") (pinfunction "~{ON}/OFF_5") (pintype "input"))
      (node (ref "IC5") (pin "6") (pinfunction "THERM_6") (pintype "bidirectional"))
      (node (ref "IC6") (pin "1") (pinfunction "DIR_1") (pintype "input"))
      (node (ref "IC6") (pin "10") (pinfunction "GND_10") (pintype "power_in"))
      (node (ref "IC6") (pin "19") (pinfunction "G_19") (pintype "input"))
      (node (ref "IC7") (pin "1") (pinfunction "DIR_1") (pintype "input"))
      (node (ref "IC7") (pin "10") (pinfunction "GND_10") (pintype "power_in"))
      (node (ref "IC7") (pin "14") (pinfunction "B5_14") (pintype "bidirectional"))
      (node (ref "IC7") (pin "15") (pinfunction "B4_15") (pintype "bidirectional"))
      (node (ref "IC7") (pin "16") (pinfunction "B3_16") (pintype "bidirectional"))
      (node (ref "IC7") (pin "17") (pinfunction "B2_17") (pintype "bidirectional"))
      (node (ref "IC7") (pin "18") (pinfunction "B1_18") (pintype "bidirectional"))
      (node (ref "IC7") (pin "19") (pinfunction "G_19") (pintype "input"))
      (node (ref "IC8") (pin "10") (pinfunction "GND_10") (pintype "power_in"))
      (node (ref "IC8") (pin "19") (pinfunction "G_19") (pintype "input"))
      (node (ref "IC8") (pin "2") (pinfunction "A1_2") (pintype "bidirectional"))
      (node (ref "IC8") (pin "3") (pinfunction "A2_3") (pintype "bidirectional"))
      (node (ref "IC8") (pin "4") (pinfunction "A3_4") (pintype "bidirectional"))
      (node (ref "JP5") (pin "1") (pinfunction "1_1") (pintype "passive"))
      (node (ref "JP7") (pin "2") (pinfunction "2_2") (pintype "passive"))
      (node (ref "JP9") (pin "10") (pinfunction "10_10") (pintype "passive"))
      (node (ref "JP9") (pin "12") (pinfunction "12_12") (pintype "passive"))
      (node (ref "JP9") (pin "14") (pinfunction "14_14") (pintype "passive"))
      (node (ref "JP9") (pin "16") (pinfunction "16_16") (pintype "passive"))
      (node (ref "JP9") (pin "18") (pinfunction "18_18") (pintype "passive"))
      (node (ref "JP9") (pin "20") (pinfunction "20_20") (pintype "passive"))
      (node (ref "JP9") (pin "22") (pinfunction "22_22") (pintype "passive"))
      (node (ref "JP9") (pin "26") (pinfunction "26_26") (pintype "passive"))
      (node (ref "R17") (pin "1") (pinfunction "1_1") (pintype "passive"))
      (node (ref "R19") (pin "1") (pinfunction "1_1") (pintype "passive"))
      (node (ref "R20") (pin "1") (pinfunction "1_1") (pintype "passive"))
      (node (ref "R9") (pin "1") (pinfunction "1_1") (pintype "passive"))
      (node (ref "U$1") (pin "15") (pinfunction "VSS_15") (pintype "bidirectional"))
      (node (ref "U$1") (pin "41") (pinfunction "VSS_41") (pintype "bidirectional"))
      (node (ref "U$1") (pin "50") (pinfunction "EV1_50") (pintype "bidirectional"))
      (node (ref "U$1") (pin "51") (pinfunction "EV2_51") (pintype "bidirectional"))
      (node (ref "U$1") (pin "67") (pinfunction "VSS_67") (pintype "bidirectional"))
      (node (ref "U$1") (pin "90") (pinfunction "VSS_90") (pintype "bidirectional"))
      (node (ref "U$2") (pin "4") (pinfunction "GND_4") (pintype "bidirectional"))
      (node (ref "U1") (pin "16") (pinfunction "VSS_16") (pintype "output"))
      (node (ref "X1") (pin "5") (pinfunction "5_5") (pintype "passive"))
      (node (ref "X2") (pin "5") (pinfunction "5_5") (pintype "passive"))
      (node (ref "Y1") (pin "2") (pinfunction "3_2") (pintype "passive"))
      (node (ref "Y1") (pin "4") (pinfunction "3_4") (pintype "passive"))
    )
    (net (code "63") (name "NO_PIN") (class "Default")
      (node (ref "JP9") (pin "24") (pinfunction "24_24") (pintype "passive"))
    )
    (net (code "64") (name "Net-(B1-PadAC1)") (class "Default")
      (node (ref "B1") (pin "AC1") (pinfunction "AC1_AC1") (pintype "passive"))
      (node (ref "F1") (pin "2") (pinfunction "2_2") (pintype "passive"))
    )
    (net (code "65") (name "Net-(CON1A-D07)") (class "Default")
      (node (ref "CON1") (pin "6") (pinfunction "D07_6") (pintype "bidirectional"))
      (node (ref "R2") (pin "1") (pinfunction "1_1") (pintype "passive"))
    )
    (net (code "66") (name "Net-(CON1A-{slash}CS1)") (class "Default")
      (node (ref "CON1") (pin "32") (pinfunction "/CS1_32") (pintype "input"))
      (node (ref "R12") (pin "1") (pinfunction "1_1") (pintype "passive"))
    )
    (net (code "67") (name "Net-(CON1A-{slash}DASP)") (class "Default")
      (node (ref "CON1") (pin "45") (pinfunction "/DASP_45") (pintype "bidirectional"))
      (node (ref "JP6") (pin "2") (pinfunction "2_2") (pintype "passive"))
    )
    (net (code "68") (name "Net-(CON1A-{slash}PDIAG)") (class "Default")
      (node (ref "CON1") (pin "46") (pinfunction "/PDIAG_46") (pintype "bidirectional"))
      (node (ref "R1") (pin "1") (pinfunction "1_1") (pintype "passive"))
    )
    (net (code "69") (name "Net-(CON1A-{slash}REG)") (class "Default")
      (node (ref "CON1") (pin "44") (pinfunction "/REG_44") (pintype "input"))
      (node (ref "R8") (pin "1") (pinfunction "1_1") (pintype "passive"))
    )
    (net (code "70") (name "Net-(CON1A-{slash}WE)") (class "Default")
      (node (ref "CON1") (pin "36") (pinfunction "/WE_36") (pintype "input"))
      (node (ref "R7") (pin "1") (pinfunction "1_1") (pintype "passive"))
    )
    (net (code "71") (name "Net-(F1-Pad1)") (class "Default")
      (node (ref "F1") (pin "1") (pinfunction "1_1") (pintype "passive"))
      (node (ref "JP8") (pin "2") (pinfunction "2_2") (pintype "passive"))
    )
    (net (code "72") (name "Net-(IC1A-C1+)") (class "Default")
      (node (ref "C4") (pin "2") (pinfunction "2_2") (pintype "passive"))
      (node (ref "IC1") (pin "1") (pinfunction "C1+_1") (pintype "bidirectional"))
    )
    (net (code "73") (name "Net-(IC1A-C1-)") (class "Default")
      (node (ref "C4") (pin "1") (pinfunction "1_1") (pintype "passive"))
      (node (ref "IC1") (pin "3") (pinfunction "C1-_3") (pintype "bidirectional"))
    )
    (net (code "74") (name "Net-(IC1A-C2+)") (class "Default")
      (node (ref "C5") (pin "2") (pinfunction "2_2") (pintype "passive"))
      (node (ref "IC1") (pin "4") (pinfunction "C2+_4") (pintype "bidirectional"))
    )
    (net (code "75") (name "Net-(IC1A-C2-)") (class "Default")
      (node (ref "C5") (pin "1") (pinfunction "1_1") (pintype "passive"))
      (node (ref "IC1") (pin "5") (pinfunction "C2-_5") (pintype "bidirectional"))
    )
    (net (code "76") (name "Net-(IC1A-R1IN)") (class "Default")
      (node (ref "IC1") (pin "13") (pinfunction "R1IN_13") (pintype "input"))
      (node (ref "X1") (pin "2") (pinfunction "2_2") (pintype "passive"))
    )
    (net (code "77") (name "Net-(IC1A-R2IN)") (class "Default")
      (node (ref "IC1") (pin "8") (pinfunction "R2IN_8") (pintype "input"))
      (node (ref "X1") (pin "8") (pinfunction "8_8") (pintype "passive"))
    )
    (net (code "78") (name "Net-(IC1A-T1OUT)") (class "Default")
      (node (ref "IC1") (pin "14") (pinfunction "T1OUT_14") (pintype "output"))
      (node (ref "X1") (pin "3") (pinfunction "3_3") (pintype "passive"))
    )
    (net (code "79") (name "Net-(IC1A-T2OUT)") (class "Default")
      (node (ref "IC1") (pin "7") (pinfunction "T2OUT_7") (pintype "output"))
      (node (ref "X1") (pin "7") (pinfunction "7_7") (pintype "passive"))
    )
    (net (code "80") (name "Net-(IC1A-V+)") (class "Default")
      (node (ref "C6") (pin "1") (pinfunction "1_1") (pintype "passive"))
      (node (ref "IC1") (pin "2") (pinfunction "V+_2") (pintype "bidirectional"))
    )
    (net (code "81") (name "Net-(IC1A-V-)") (class "Default")
      (node (ref "C25") (pin "1") (pinfunction "1_1") (pintype "passive"))
      (node (ref "IC1") (pin "6") (pinfunction "V-_6") (pintype "bidirectional"))
    )
    (net (code "82") (name "Net-(IC2A-C1+)") (class "Default")
      (node (ref "C7") (pin "2") (pinfunction "2_2") (pintype "passive"))
      (node (ref "IC2") (pin "1") (pinfunction "C1+_1") (pintype "bidirectional"))
    )
    (net (code "83") (name "Net-(IC2A-C1-)") (class "Default")
      (node (ref "C7") (pin "1") (pinfunction "1_1") (pintype "passive"))
      (node (ref "IC2") (pin "3") (pinfunction "C1-_3") (pintype "bidirectional"))
    )
    (net (code "84") (name "Net-(IC2A-C2+)") (class "Default")
      (node (ref "C8") (pin "2") (pinfunction "2_2") (pintype "passive"))
      (node (ref "IC2") (pin "4") (pinfunction "C2+_4") (pintype "bidirectional"))
    )
    (net (code "85") (name "Net-(IC2A-C2-)") (class "Default")
      (node (ref "C8") (pin "1") (pinfunction "1_1") (pintype "passive"))
      (node (ref "IC2") (pin "5") (pinfunction "C2-_5") (pintype "bidirectional"))
    )
    (net (code "86") (name "Net-(IC2A-R1IN)") (class "Default")
      (node (ref "IC2") (pin "13") (pinfunction "R1IN_13") (pintype "input"))
      (node (ref "X2") (pin "2") (pinfunction "2_2") (pintype "passive"))
    )
    (net (code "87") (name "Net-(IC2A-R2IN)") (class "Default")
      (node (ref "IC2") (pin "8") (pinfunction "R2IN_8") (pintype "input"))
      (node (ref "X2") (pin "8") (pinfunction "8_8") (pintype "passive"))
    )
    (net (code "88") (name "Net-(IC2A-T1OUT)") (class "Default")
      (node (ref "IC2") (pin "14") (pinfunction "T1OUT_14") (pintype "output"))
      (node (ref "X2") (pin "3") (pinfunction "3_3") (pintype "passive"))
    )
    (net (code "89") (name "Net-(IC2A-T2OUT)") (class "Default")
      (node (ref "IC2") (pin "7") (pinfunction "T2OUT_7") (pintype "output"))
      (node (ref "X2") (pin "7") (pinfunction "7_7") (pintype "passive"))
    )
    (net (code "90") (name "Net-(IC2A-V+)") (class "Default")
      (node (ref "C9") (pin "1") (pinfunction "1_1") (pintype "passive"))
      (node (ref "IC2") (pin "2") (pinfunction "V+_2") (pintype "bidirectional"))
    )
    (net (code "91") (name "Net-(IC2A-V-)") (class "Default")
      (node (ref "C10") (pin "1") (pinfunction "1_1") (pintype "passive"))
      (node (ref "IC2") (pin "6") (pinfunction "V-_6") (pintype "bidirectional"))
    )
    (net (code "92") (name "Net-(IC5-OUT)") (class "Default")
      (node (ref "D1") (pin "C") (pinfunction "C_C") (pintype "passive"))
      (node (ref "IC5") (pin "2") (pinfunction "OUT_2") (pintype "output"))
      (node (ref "L2") (pin "P$1") (pinfunction "1_P$1") (pintype "passive"))
    )
    (net (code "93") (name "Net-(IC5-VIN)") (class "Default")
      (node (ref "B1") (pin "+") (pinfunction "+_+") (pintype "passive"))
      (node (ref "C21") (pin "+") (pinfunction "+_+") (pintype "passive"))
      (node (ref "C23") (pin "1") (pinfunction "1_1") (pintype "passive"))
      (node (ref "IC5") (pin "1") (pinfunction "VIN_1") (pintype "input"))
    )
    (net (code "94") (name "Net-(IC8A-B4)") (class "Default")
      (node (ref "IC8") (pin "15") (pinfunction "B4_15") (pintype "bidirectional"))
      (node (ref "R23") (pin "1") (pinfunction "1_1") (pintype "passive"))
    )
    (net (code "95") (name "Net-(IC8A-B7)") (class "Default")
      (node (ref "IC8") (pin "12") (pinfunction "B7_12") (pintype "bidirectional"))
      (node (ref "R22") (pin "1") (pinfunction "1_1") (pintype "passive"))
    )
    (net (code "96") (name "Net-(IC8A-DIR)") (class "Default")
      (node (ref "IC8") (pin "1") (pinfunction "DIR_1") (pintype "input"))
      (node (ref "R11") (pin "1") (pinfunction "1_1") (pintype "passive"))
    )
    (net (code "97") (name "Net-(J2-GND)") (class "Default")
      (node (ref "B1") (pin "AC2") (pinfunction "AC2_AC2") (pintype "passive"))
      (node (ref "J2") (pin "GND@1") (pinfunction "GNDBREAK_GND@1") (pintype "bidirectional"))
      (node (ref "J2") (pin "GND@2") (pinfunction "GND_GND@2") (pintype "bidirectional"))
    )
    (net (code "98") (name "Net-(J2-PadPWR)") (class "Default")
      (node (ref "J2") (pin "PWR") (pinfunction "PWR_PWR") (pintype "bidirectional"))
      (node (ref "JP8") (pin "1") (pinfunction "1_1") (pintype "passive"))
    )
    (net (code "99") (name "Net-(JP6-Pad1)") (class "Default")
      (node (ref "JP6") (pin "1") (pinfunction "1_1") (pintype "passive"))
      (node (ref "R13") (pin "1") (pinfunction "1_1") (pintype "passive"))
    )
    (net (code "100") (name "Net-(U$1-CKA0{slash}{slash}DREQ0)") (class "Default")
      (node (ref "R18") (pin "1") (pinfunction "1_1") (pintype "passive"))
      (node (ref "U$1") (pin "40") (pinfunction "CKA0//DREQ0_40") (pintype "bidirectional"))
    )
    (net (code "101") (name "Net-(U$1-ST)") (class "Default")
      (node (ref "R14") (pin "1") (pinfunction "1_1") (pintype "passive"))
      (node (ref "U$1") (pin "1") (pinfunction "ST_1") (pintype "bidirectional"))
    )
    (net (code "102") (name "Net-(U$1-{slash}DREQ1)") (class "Default")
      (node (ref "R15") (pin "1") (pinfunction "1_1") (pintype "passive"))
      (node (ref "U$1") (pin "45") (pinfunction "/DREQ1_45") (pintype "bidirectional"))
    )
    (net (code "103") (name "Net-(U$2-CT)") (class "Default")
      (node (ref "C18") (pin "1") (pinfunction "1_1") (pintype "passive"))
      (node (ref "U$2") (pin "3") (pinfunction "CT_3") (pintype "bidirectional"))
    )
    (net (code "104") (name "Net-(U$2-REF)") (class "Default")
      (node (ref "C19") (pin "1") (pinfunction "1_1") (pintype "passive"))
      (node (ref "U$2") (pin "1") (pinfunction "REF_1") (pintype "bidirectional"))
    )
    (net (code "105") (name "Net-(U$2-RESET)") (class "Default")
      (node (ref "R9") (pin "2") (pinfunction "2_2") (pintype "passive"))
      (node (ref "U$2") (pin "6") (pinfunction "RESET_6") (pintype "bidirectional"))
    )
    (net (code "106") (name "Net-(U$2-~{RESIN})") (class "Default")
      (node (ref "JP5") (pin "2") (pinfunction "2_2") (pintype "passive"))
      (node (ref "R10") (pin "1") (pinfunction "1_1") (pintype "passive"))
      (node (ref "U$2") (pin "2") (pinfunction "~{RESIN}_2") (pintype "bidirectional"))
    )
    (net (code "107") (name "PD0") (class "Default")
      (node (ref "IC6") (pin "2") (pinfunction "A1_2") (pintype "bidirectional"))
      (node (ref "JP9") (pin "3") (pinfunction "3_3") (pintype "passive"))
    )
    (net (code "108") (name "PD0_IN") (class "Default")
      (node (ref "IC6") (pin "18") (pinfunction "B1_18") (pintype "bidirectional"))
      (node (ref "U$1") (pin "52") (pinfunction "PA0/HD0_52") (pintype "bidirectional"))
    )
    (net (code "109") (name "PD1") (class "Default")
      (node (ref "IC6") (pin "3") (pinfunction "A2_3") (pintype "bidirectional"))
      (node (ref "JP9") (pin "5") (pinfunction "5_5") (pintype "passive"))
    )
    (net (code "110") (name "PD1_IN") (class "Default")
      (node (ref "IC6") (pin "17") (pinfunction "B2_17") (pintype "bidirectional"))
      (node (ref "U$1") (pin "53") (pinfunction "PA1/HD1_53") (pintype "bidirectional"))
    )
    (net (code "111") (name "PD2") (class "Default")
      (node (ref "IC6") (pin "4") (pinfunction "A3_4") (pintype "bidirectional"))
      (node (ref "JP9") (pin "7") (pinfunction "7_7") (pintype "passive"))
    )
    (net (code "112") (name "PD2_IN") (class "Default")
      (node (ref "IC6") (pin "16") (pinfunction "B3_16") (pintype "bidirectional"))
      (node (ref "U$1") (pin "54") (pinfunction "PA2/HD2_54") (pintype "bidirectional"))
    )
    (net (code "113") (name "PD3") (class "Default")
      (node (ref "IC6") (pin "5") (pinfunction "A4_5") (pintype "bidirectional"))
      (node (ref "JP9") (pin "9") (pinfunction "9_9") (pintype "passive"))
    )
    (net (code "114") (name "PD3_IN") (class "Default")
      (node (ref "IC6") (pin "15") (pinfunction "B4_15") (pintype "bidirectional"))
      (node (ref "U$1") (pin "55") (pinfunction "PA3/HD3_55") (pintype "bidirectional"))
    )
    (net (code "115") (name "PD4") (class "Default")
      (node (ref "IC6") (pin "6") (pinfunction "A5_6") (pintype "bidirectional"))
      (node (ref "JP9") (pin "11") (pinfunction "11_11") (pintype "passive"))
    )
    (net (code "116") (name "PD4_IN") (class "Default")
      (node (ref "IC6") (pin "14") (pinfunction "B5_14") (pintype "bidirectional"))
      (node (ref "U$1") (pin "56") (pinfunction "PA4/HD4_56") (pintype "bidirectional"))
    )
    (net (code "117") (name "PD5") (class "Default")
      (node (ref "IC6") (pin "7") (pinfunction "A6_7") (pintype "bidirectional"))
      (node (ref "JP9") (pin "13") (pinfunction "13_13") (pintype "passive"))
    )
    (net (code "118") (name "PD5_IN") (class "Default")
      (node (ref "IC6") (pin "13") (pinfunction "B6_13") (pintype "bidirectional"))
      (node (ref "U$1") (pin "57") (pinfunction "PA5/HD5_57") (pintype "bidirectional"))
    )
    (net (code "119") (name "PD6") (class "Default")
      (node (ref "IC6") (pin "8") (pinfunction "A7_8") (pintype "bidirectional"))
      (node (ref "JP9") (pin "15") (pinfunction "15_15") (pintype "passive"))
    )
    (net (code "120") (name "PD6_IN") (class "Default")
      (node (ref "IC6") (pin "12") (pinfunction "B7_12") (pintype "bidirectional"))
      (node (ref "U$1") (pin "58") (pinfunction "PA6/HD6_58") (pintype "bidirectional"))
    )
    (net (code "121") (name "PD7") (class "Default")
      (node (ref "IC6") (pin "9") (pinfunction "A8_9") (pintype "bidirectional"))
      (node (ref "JP9") (pin "17") (pinfunction "17_17") (pintype "passive"))
    )
    (net (code "122") (name "PD7_IN") (class "Default")
      (node (ref "IC6") (pin "11") (pinfunction "B8_11") (pintype "bidirectional"))
      (node (ref "U$1") (pin "59") (pinfunction "PA7/HD7_59") (pintype "bidirectional"))
    )
    (net (code "123") (name "PE") (class "Default")
      (node (ref "IC8") (pin "7") (pinfunction "A6_7") (pintype "bidirectional"))
      (node (ref "JP9") (pin "23") (pinfunction "23_23") (pintype "passive"))
      (node (ref "R19") (pin "2") (pinfunction "2_2") (pintype "passive"))
    )
    (net (code "124") (name "PE_OUT") (class "Default")
      (node (ref "IC8") (pin "13") (pinfunction "B6_13") (pintype "bidirectional"))
      (node (ref "U$1") (pin "34") (pinfunction "/DCD0/PB2_34") (pintype "bidirectional"))
    )
    (net (code "125") (name "PR_ACK_OUT") (class "Default")
      (node (ref "IC8") (pin "11") (pinfunction "B8_11") (pintype "bidirectional"))
      (node (ref "U$1") (pin "36") (pinfunction "RXA0/PB4_36") (pintype "bidirectional"))
    )
    (net (code "126") (name "RTS1") (class "Default")
      (node (ref "IC2") (pin "10") (pinfunction "T2IN_10") (pintype "input"))
      (node (ref "U$1") (pin "62") (pinfunction "/MWR/PC2//RTSA_62") (pintype "bidirectional"))
    )
    (net (code "127") (name "RTS2") (class "Default")
      (node (ref "IC1") (pin "10") (pinfunction "T2IN_10") (pintype "input"))
      (node (ref "U$1") (pin "47") (pinfunction "/TEND1//RTSB//HRXRDY_47") (pintype "bidirectional"))
    )
    (net (code "128") (name "RX") (class "Default")
      (node (ref "JP11") (pin "1") (pinfunction "1_1") (pintype "passive"))
    )
    (net (code "129") (name "RXD1") (class "Default")
      (node (ref "IC2") (pin "12") (pinfunction "R1OUT_12") (pintype "output"))
      (node (ref "U$1") (pin "71") (pinfunction "RXDA_71") (pintype "bidirectional"))
    )
    (net (code "130") (name "RXD2") (class "Default")
      (node (ref "IC1") (pin "12") (pinfunction "R1OUT_12") (pintype "output"))
      (node (ref "U$1") (pin "78") (pinfunction "RXDB/HA1_78") (pintype "bidirectional"))
    )
    (net (code "131") (name "SLCT") (class "Default")
      (node (ref "IC8") (pin "6") (pinfunction "A5_6") (pintype "bidirectional"))
      (node (ref "JP9") (pin "25") (pinfunction "25_25") (pintype "passive"))
      (node (ref "R17") (pin "2") (pinfunction "2_2") (pintype "passive"))
    )
    (net (code "132") (name "SLCT_OUT") (class "Default")
      (node (ref "IC8") (pin "14") (pinfunction "B5_14") (pintype "bidirectional"))
      (node (ref "U$1") (pin "33") (pinfunction "/CTS0/PB1_33") (pintype "bidirectional"))
    )
    (net (code "133") (name "TX") (class "Default")
      (node (ref "JP11") (pin "2") (pinfunction "2_2") (pintype "passive"))
    )
    (net (code "134") (name "TXD1") (class "Default")
      (node (ref "IC2") (pin "11") (pinfunction "T1IN_11") (pintype "input"))
      (node (ref "U$1") (pin "73") (pinfunction "TXDA_73") (pintype "bidirectional"))
    )
    (net (code "135") (name "TXD2") (class "Default")
      (node (ref "IC1") (pin "11") (pinfunction "T1IN_11") (pintype "input"))
      (node (ref "U$1") (pin "76") (pinfunction "TXDB//HDDIS_76") (pintype "bidirectional"))
    )
    (net (code "136") (name "XTAL") (class "Default")
      (node (ref "C32") (pin "1") (pinfunction "1_1") (pintype "passive"))
      (node (ref "U$1") (pin "91") (pinfunction "XTAL_91") (pintype "bidirectional"))
      (node (ref "Y1") (pin "1") (pinfunction "2_1") (pintype "passive"))
    )
    (net (code "137") (name "unconnected-(CON1A-D08-Pad47)") (class "Default")
      (node (ref "CON1") (pin "47") (pinfunction "D08_47") (pintype "bidirectional"))
    )
    (net (code "138") (name "unconnected-(CON1A-D09-Pad48)") (class "Default")
      (node (ref "CON1") (pin "48") (pinfunction "D09_48") (pintype "bidirectional"))
    )
    (net (code "139") (name "unconnected-(CON1A-D10-Pad49)") (class "Default")
      (node (ref "CON1") (pin "49") (pinfunction "D10_49") (pintype "bidirectional"))
    )
    (net (code "140") (name "unconnected-(CON1A-D11-Pad27)") (class "Default")
      (node (ref "CON1") (pin "27") (pinfunction "D11_27") (pintype "bidirectional"))
    )
    (net (code "141") (name "unconnected-(CON1A-D12-Pad28)") (class "Default")
      (node (ref "CON1") (pin "28") (pinfunction "D12_28") (pintype "bidirectional"))
    )
    (net (code "142") (name "unconnected-(CON1A-D13-Pad29)") (class "Default")
      (node (ref "CON1") (pin "29") (pinfunction "D13_29") (pintype "bidirectional"))
    )
    (net (code "143") (name "unconnected-(CON1A-D14-Pad30)") (class "Default")
      (node (ref "CON1") (pin "30") (pinfunction "D14_30") (pintype "bidirectional"))
    )
    (net (code "144") (name "unconnected-(CON1A-D15-Pad31)") (class "Default")
      (node (ref "CON1") (pin "31") (pinfunction "D15_31") (pintype "bidirectional"))
    )
    (net (code "145") (name "unconnected-(CON1A-INTRQ-Pad37)") (class "Default")
      (node (ref "CON1") (pin "37") (pinfunction "INTRQ_37") (pintype "output"))
    )
    (net (code "146") (name "unconnected-(CON1A-IORDY-Pad42)") (class "Default")
      (node (ref "CON1") (pin "42") (pinfunction "IORDY_42") (pintype "output"))
    )
    (net (code "147") (name "unconnected-(CON1A-{slash}CD1-Pad26)") (class "Default")
      (node (ref "CON1") (pin "26") (pinfunction "/CD1_26") (pintype "output"))
    )
    (net (code "148") (name "unconnected-(CON1A-{slash}CD2-Pad25)") (class "Default")
      (node (ref "CON1") (pin "25") (pinfunction "/CD2_25") (pintype "output"))
    )
    (net (code "149") (name "unconnected-(CON1A-{slash}INPACK-Pad43)") (class "Default")
      (node (ref "CON1") (pin "43") (pinfunction "/INPACK_43") (pintype "output"))
    )
    (net (code "150") (name "unconnected-(CON1A-{slash}IOCS16-Pad24)") (class "Default")
      (node (ref "CON1") (pin "24") (pinfunction "/IOCS16_24") (pintype "output"))
    )
    (net (code "151") (name "unconnected-(CON1A-{slash}VS1-Pad33)") (class "Default")
      (node (ref "CON1") (pin "33") (pinfunction "/VS1_33") (pintype "output"))
    )
    (net (code "152") (name "unconnected-(CON1A-{slash}VS2-Pad40)") (class "Default")
      (node (ref "CON1") (pin "40") (pinfunction "/VS2_40") (pintype "output"))
    )
    (net (code "153") (name "unconnected-(IC7A-A1-Pad2)") (class "Default")
      (node (ref "IC7") (pin "2") (pinfunction "A1_2") (pintype "bidirectional"))
    )
    (net (code "154") (name "unconnected-(IC7A-A2-Pad3)") (class "Default")
      (node (ref "IC7") (pin "3") (pinfunction "A2_3") (pintype "bidirectional"))
    )
    (net (code "155") (name "unconnected-(IC7A-A3-Pad4)") (class "Default")
      (node (ref "IC7") (pin "4") (pinfunction "A3_4") (pintype "bidirectional"))
    )
    (net (code "156") (name "unconnected-(IC7A-A4-Pad5)") (class "Default")
      (node (ref "IC7") (pin "5") (pinfunction "A4_5") (pintype "bidirectional"))
    )
    (net (code "157") (name "unconnected-(IC7A-A5-Pad6)") (class "Default")
      (node (ref "IC7") (pin "6") (pinfunction "A5_6") (pintype "bidirectional"))
    )
    (net (code "158") (name "unconnected-(IC8A-B1-Pad18)") (class "Default")
      (node (ref "IC8") (pin "18") (pinfunction "B1_18") (pintype "bidirectional"))
    )
    (net (code "159") (name "unconnected-(IC8A-B2-Pad17)") (class "Default")
      (node (ref "IC8") (pin "17") (pinfunction "B2_17") (pintype "bidirectional"))
    )
    (net (code "160") (name "unconnected-(IC8A-B3-Pad16)") (class "Default")
      (node (ref "IC8") (pin "16") (pinfunction "B3_16") (pintype "bidirectional"))
    )
    (net (code "161") (name "unconnected-(JP2-Pad7)") (class "Default")
      (node (ref "JP2") (pin "7") (pinfunction "7_7") (pintype "passive"))
    )
    (net (code "162") (name "unconnected-(JP2-Pad8)") (class "Default")
      (node (ref "JP2") (pin "8") (pinfunction "8_8") (pintype "passive"))
    )
    (net (code "163") (name "unconnected-(U$1-CKA1{slash}{slash}TEND0-Pad42)") (class "Default")
      (node (ref "U$1") (pin "42") (pinfunction "CKA1//TEND0_42") (pintype "bidirectional"))
    )
    (net (code "164") (name "unconnected-(U$1-CKS{slash}{slash}W{slash}{slash}REQB{slash}{slash}HTXRDY-Pad44)") (class "Default")
      (node (ref "U$1") (pin "44") (pinfunction "CKS//W//REQB//HTXRDY_44") (pintype "bidirectional"))
    )
    (net (code "165") (name "unconnected-(U$1-E-Pad85)") (class "Default")
      (node (ref "U$1") (pin "85") (pinfunction "E_85") (pintype "bidirectional"))
    )
    (net (code "166") (name "unconnected-(U$1-IEI-Pad69)") (class "Default")
      (node (ref "U$1") (pin "69") (pinfunction "IEI_69") (pintype "bidirectional"))
    )
    (net (code "167") (name "unconnected-(U$1-TRXCA-Pad72)") (class "Default")
      (node (ref "U$1") (pin "72") (pinfunction "TRXCA_72") (pintype "bidirectional"))
    )
    (net (code "168") (name "unconnected-(U$1-TXS{slash}{slash}DTR{slash}{slash}REQB{slash}HINTR-Pad43)") (class "Default")
      (node (ref "U$1") (pin "43") (pinfunction "TXS//DTR//REQB/HINTR_43") (pintype "bidirectional"))
    )
    (net (code "169") (name "unconnected-(U$1-{slash}DCDA{slash}PC0-Pad64)") (class "Default")
      (node (ref "U$1") (pin "64") (pinfunction "/DCDA/PC0_64") (pintype "bidirectional"))
    )
    (net (code "170") (name "unconnected-(U$1-{slash}DCDB{slash}{slash}HRD-Pad74)") (class "Default")
      (node (ref "U$1") (pin "74") (pinfunction "/DCDB//HRD_74") (pintype "bidirectional"))
    )
    (net (code "171") (name "unconnected-(U$1-{slash}DTR{slash}{slash}REQA{slash}PC3-Pad61)") (class "Default")
      (node (ref "U$1") (pin "61") (pinfunction "/DTR//REQA/PC3_61") (pintype "bidirectional"))
    )
    (net (code "172") (name "unconnected-(U$1-{slash}IOCS{slash}IEO-Pad68)") (class "Default")
      (node (ref "U$1") (pin "68") (pinfunction "/IOCS/IEO_68") (pintype "bidirectional"))
    )
    (net (code "173") (name "unconnected-(U$1-{slash}MRD{slash}{slash}MREQ-Pad84)") (class "Default")
      (node (ref "U$1") (pin "84") (pinfunction "/MRD//MREQ_84") (pintype "bidirectional"))
    )
    (net (code "174") (name "unconnected-(U$1-{slash}RTXCA-Pad66)") (class "Default")
      (node (ref "U$1") (pin "66") (pinfunction "/RTXCA_66") (pintype "bidirectional"))
    )
    (net (code "175") (name "unconnected-(U$1-{slash}RTXCB{slash}HA2-Pad79)") (class "Default")
      (node (ref "U$1") (pin "79") (pinfunction "/RTXCB/HA2_79") (pintype "bidirectional"))
    )
    (net (code "176") (name "unconnected-(U$1-{slash}SYNCA{slash}PC4-Pad65)") (class "Default")
      (node (ref "U$1") (pin "65") (pinfunction "/SYNCA/PC4_65") (pintype "bidirectional"))
    )
    (net (code "177") (name "unconnected-(U$1-{slash}SYNCB{slash}{slash}HCS-Pad80)") (class "Default")
      (node (ref "U$1") (pin "80") (pinfunction "/SYNCB//HCS_80") (pintype "bidirectional"))
    )
    (net (code "178") (name "unconnected-(U$1-{slash}TRXCB{slash}HA0-Pad77)") (class "Default")
      (node (ref "U$1") (pin "77") (pinfunction "/TRXCB/HA0_77") (pintype "bidirectional"))
    )
    (net (code "179") (name "unconnected-(U$1-{slash}W{slash}{slash}REQA{slash}PC5-Pad60)") (class "Default")
      (node (ref "U$1") (pin "60") (pinfunction "/W//REQA/PC5_60") (pintype "bidirectional"))
    )
    (net (code "180") (name "unconnected-(X1-Pad1)") (class "Default")
      (node (ref "X1") (pin "1") (pinfunction "1_1") (pintype "passive"))
    )
    (net (code "181") (name "unconnected-(X1-Pad4)") (class "Default")
      (node (ref "X1") (pin "4") (pinfunction "4_4") (pintype "passive"))
    )
    (net (code "182") (name "unconnected-(X1-Pad6)") (class "Default")
      (node (ref "X1") (pin "6") (pinfunction "6_6") (pintype "passive"))
    )
    (net (code "183") (name "unconnected-(X1-Pad9)") (class "Default")
      (node (ref "X1") (pin "9") (pinfunction "9_9") (pintype "passive"))
    )
    (net (code "184") (name "unconnected-(X2-Pad1)") (class "Default")
      (node (ref "X2") (pin "1") (pinfunction "1_1") (pintype "passive"))
    )
    (net (code "185") (name "unconnected-(X2-Pad4)") (class "Default")
      (node (ref "X2") (pin "4") (pinfunction "4_4") (pintype "passive"))
    )
    (net (code "186") (name "unconnected-(X2-Pad6)") (class "Default")
      (node (ref "X2") (pin "6") (pinfunction "6_6") (pintype "passive"))
    )
    (net (code "187") (name "unconnected-(X2-Pad9)") (class "Default")
      (node (ref "X2") (pin "9") (pinfunction "9_9") (pintype "passive"))
    )
    (net (code "188") (name "{slash}ACK") (class "Default")
      (node (ref "IC8") (pin "9") (pinfunction "A8_9") (pintype "bidirectional"))
      (node (ref "JP9") (pin "19") (pinfunction "19_19") (pintype "passive"))
      (node (ref "R21") (pin "1") (pinfunction "1_1") (pintype "passive"))
    )
    (net (code "189") (name "{slash}AFD") (class "Default")
      (node (ref "JP9") (pin "2") (pinfunction "2_2") (pintype "passive"))
    )
    (net (code "190") (name "{slash}ERR") (class "Default")
      (node (ref "IC8") (pin "5") (pinfunction "A4_5") (pintype "bidirectional"))
      (node (ref "JP9") (pin "4") (pinfunction "4_4") (pintype "passive"))
      (node (ref "R16") (pin "1") (pinfunction "1_1") (pintype "passive"))
    )
    (net (code "191") (name "{slash}ERR_OUT") (class "Default")
      (node (ref "R23") (pin "2") (pinfunction "2_2") (pintype "passive"))
      (node (ref "U$1") (pin "32") (pinfunction "/RTS0/PB0_32") (pintype "bidirectional"))
    )
    (net (code "192") (name "{slash}INIT") (class "Default")
      (node (ref "IC7") (pin "8") (pinfunction "A7_8") (pintype "bidirectional"))
      (node (ref "JP9") (pin "6") (pinfunction "6_6") (pintype "passive"))
    )
    (net (code "193") (name "{slash}PRINTER_INIT_IN") (class "Default")
      (node (ref "IC7") (pin "12") (pinfunction "B7_12") (pintype "bidirectional"))
      (node (ref "U$1") (pin "38") (pinfunction "RXA1/PB6_38") (pintype "bidirectional"))
    )
    (net (code "194") (name "{slash}PSTB") (class "Default")
      (node (ref "IC7") (pin "9") (pinfunction "A8_9") (pintype "bidirectional"))
      (node (ref "JP9") (pin "1") (pinfunction "1_1") (pintype "passive"))
    )
    (net (code "195") (name "{slash}PSTB_IN") (class "Default")
      (node (ref "IC7") (pin "11") (pinfunction "B8_11") (pintype "bidirectional"))
      (node (ref "U$1") (pin "39") (pinfunction "RXS//CTS1/PB7_39") (pintype "bidirectional"))
    )
    (net (code "196") (name "{slash}SLIN") (class "Default")
      (node (ref "IC7") (pin "7") (pinfunction "A6_7") (pintype "bidirectional"))
      (node (ref "JP9") (pin "8") (pinfunction "8_8") (pintype "passive"))
    )
    (net (code "197") (name "{slash}SLIN_IN") (class "Default")
      (node (ref "IC7") (pin "13") (pinfunction "B6_13") (pintype "bidirectional"))
      (node (ref "U$1") (pin "37") (pinfunction "TXA1/PB5_37") (pintype "bidirectional"))
    )
  )
)
